# DigitalCarrierPlug.net
KiCad netlist of a schematic drawn in Altium Designer
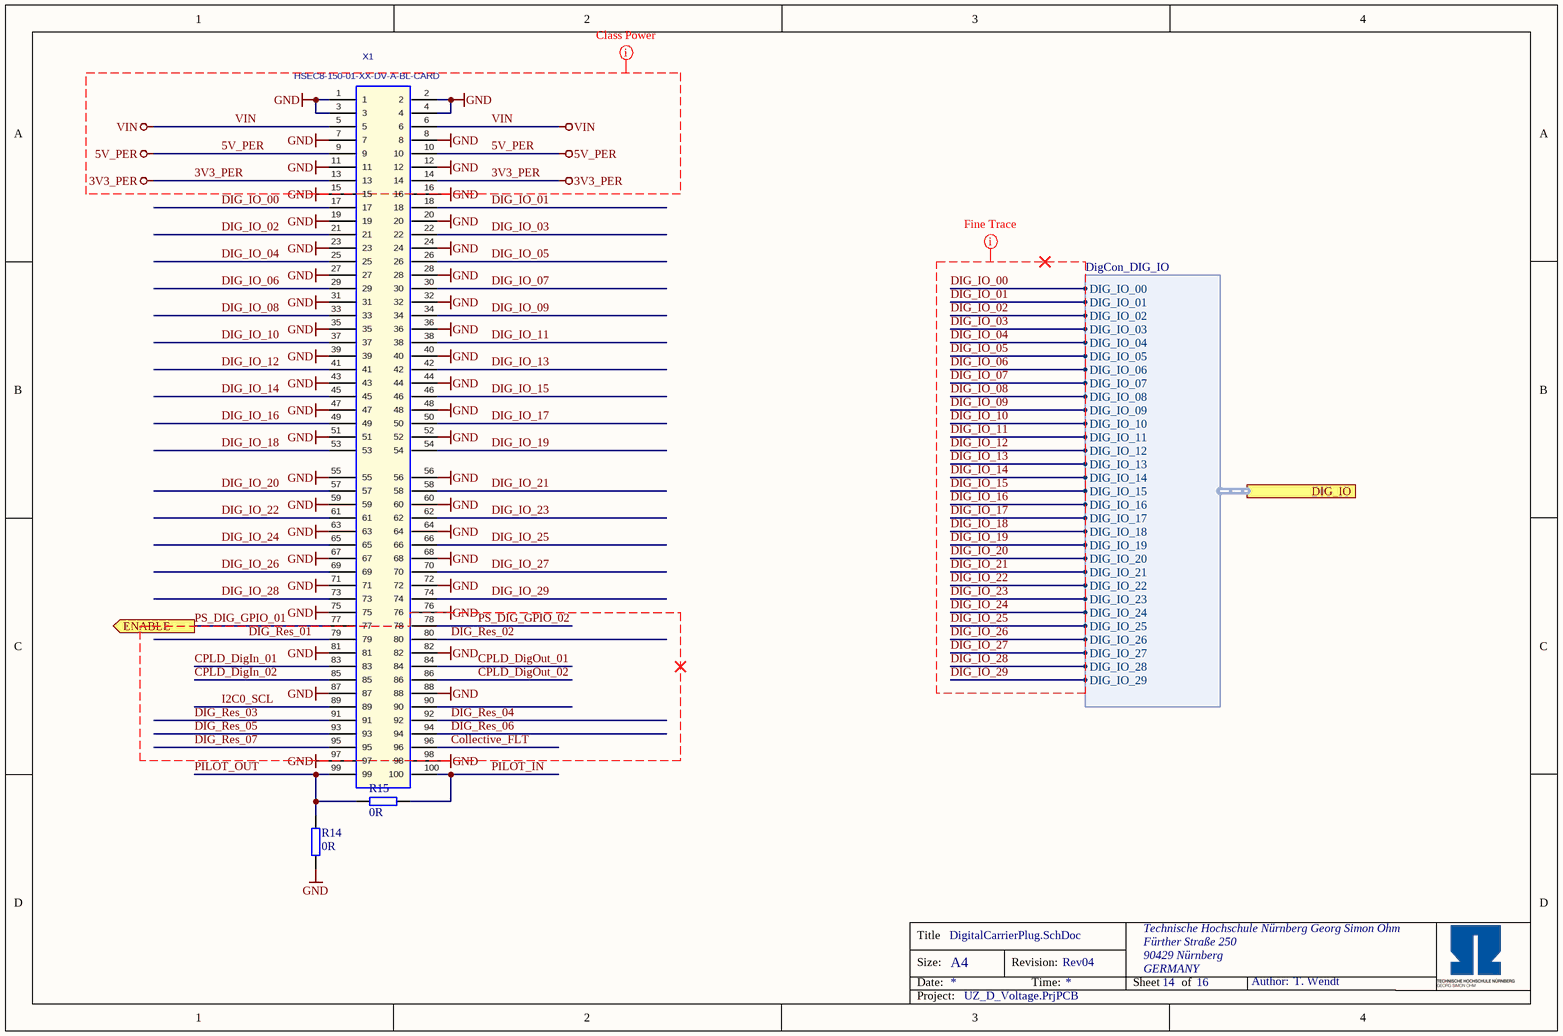
[diagram p0: DigitalCarrierPlug.SchDoc]

(export (version "E")
  (design (tool "Eeschema 10.0.6"))
  (components
    (comp (ref "R14")
      (value "0R")
      (footprint "RES 0603_1608")
      (description "SMD resistor E24 series")
      (fields
        (field (name "MANUFACTURER PART NUMBER") "RC0603JR-070RL")
        (field (name "MANUFACTURER") "YAGEO")
        (field (name "CREATED FROM") "MGremer")
      )
      (libsource (lib "user") (part "Resistor"))
    )
    (comp (ref "R15")
      (value "0R")
      (footprint "RES 0603_1608")
      (description "SMD resistor E24 series")
      (fields
        (field (name "MANUFACTURER PART NUMBER") "RC0603JR-070RL")
        (field (name "MANUFACTURER") "YAGEO")
        (field (name "CREATED FROM") "MGremer")
      )
      (libsource (lib "user") (part "Resistor"))
    )
    (comp (ref "X1")
      (value "HSEC8-150-01-XX-DV-A-BL-CARD")
      (footprint "HSEC8-150-01-XX-DV-A-BL-CARD")
      (description "Mating Card Layout for HSEC8-150-01-XX-DV-A-BL")
      (fields
        (field (name "MANUFACTURER") "SAMTEC")
        (field (name "CREATED") "2018_04_23_AGeiger")
        (field (name "CREATED FROM") "T. Wendt")
      )
      (libsource (lib "user") (part "HSEC8-150-01-XX-DV-A-BL-CARD"))
    )
  )
  (nets
    (net (code "2") (name "/CPLD_DigIn_01") (class "Default")
      (node (ref "X1") (pin "83") (pinfunction "83_83") (pintype "passive"))
    )
    (net (code "3") (name "/CPLD_DigIn_02") (class "Default")
      (node (ref "X1") (pin "85") (pinfunction "85_85") (pintype "passive"))
    )
    (net (code "4") (name "/CPLD_DigOut_01") (class "Default")
      (node (ref "X1") (pin "84") (pinfunction "84_84") (pintype "passive"))
    )
    (net (code "5") (name "/CPLD_DigOut_02") (class "Default")
      (node (ref "X1") (pin "86") (pinfunction "86_86") (pintype "passive"))
    )
    (net (code "6") (name "/Collective_FLT") (class "Default")
      (node (ref "X1") (pin "96") (pinfunction "96_96") (pintype "passive"))
    )
    (net (code "7") (name "/DIG_IO_00") (class "Default")
      (node (ref "X1") (pin "17") (pinfunction "17_17") (pintype "passive"))
    )
    (net (code "8") (name "/DIG_IO_01") (class "Default")
      (node (ref "X1") (pin "18") (pinfunction "18_18") (pintype "passive"))
    )
    (net (code "9") (name "/DIG_IO_02") (class "Default")
      (node (ref "X1") (pin "21") (pinfunction "21_21") (pintype "passive"))
    )
    (net (code "10") (name "/DIG_IO_03") (class "Default")
      (node (ref "X1") (pin "22") (pinfunction "22_22") (pintype "passive"))
    )
    (net (code "11") (name "/DIG_IO_04") (class "Default")
      (node (ref "X1") (pin "25") (pinfunction "25_25") (pintype "passive"))
    )
    (net (code "12") (name "/DIG_IO_05") (class "Default")
      (node (ref "X1") (pin "26") (pinfunction "26_26") (pintype "passive"))
    )
    (net (code "13") (name "/DIG_IO_06") (class "Default")
      (node (ref "X1") (pin "29") (pinfunction "29_29") (pintype "passive"))
    )
    (net (code "14") (name "/DIG_IO_07") (class "Default")
      (node (ref "X1") (pin "30") (pinfunction "30_30") (pintype "passive"))
    )
    (net (code "15") (name "/DIG_IO_08") (class "Default")
      (node (ref "X1") (pin "33") (pinfunction "33_33") (pintype "passive"))
    )
    (net (code "16") (name "/DIG_IO_09") (class "Default")
      (node (ref "X1") (pin "34") (pinfunction "34_34") (pintype "passive"))
    )
    (net (code "17") (name "/DIG_IO_10") (class "Default")
      (node (ref "X1") (pin "37") (pinfunction "37_37") (pintype "passive"))
    )
    (net (code "18") (name "/DIG_IO_11") (class "Default")
      (node (ref "X1") (pin "38") (pinfunction "38_38") (pintype "passive"))
    )
    (net (code "19") (name "/DIG_IO_12") (class "Default")
      (node (ref "X1") (pin "41") (pinfunction "41_41") (pintype "passive"))
    )
    (net (code "20") (name "/DIG_IO_13") (class "Default")
      (node (ref "X1") (pin "42") (pinfunction "42_42") (pintype "passive"))
    )
    (net (code "21") (name "/DIG_IO_14") (class "Default")
      (node (ref "X1") (pin "45") (pinfunction "45_45") (pintype "passive"))
    )
    (net (code "22") (name "/DIG_IO_15") (class "Default")
      (node (ref "X1") (pin "46") (pinfunction "46_46") (pintype "passive"))
    )
    (net (code "23") (name "/DIG_IO_16") (class "Default")
      (node (ref "X1") (pin "49") (pinfunction "49_49") (pintype "passive"))
    )
    (net (code "24") (name "/DIG_IO_17") (class "Default")
      (node (ref "X1") (pin "50") (pinfunction "50_50") (pintype "passive"))
    )
    (net (code "25") (name "/DIG_IO_18") (class "Default")
      (node (ref "X1") (pin "53") (pinfunction "53_53") (pintype "passive"))
    )
    (net (code "26") (name "/DIG_IO_19") (class "Default")
      (node (ref "X1") (pin "54") (pinfunction "54_54") (pintype "passive"))
    )
    (net (code "27") (name "/DIG_IO_20") (class "Default")
      (node (ref "X1") (pin "57") (pinfunction "57_57") (pintype "passive"))
    )
    (net (code "28") (name "/DIG_IO_21") (class "Default")
      (node (ref "X1") (pin "58") (pinfunction "58_58") (pintype "passive"))
    )
    (net (code "29") (name "/DIG_IO_22") (class "Default")
      (node (ref "X1") (pin "61") (pinfunction "61_61") (pintype "passive"))
    )
    (net (code "30") (name "/DIG_IO_23") (class "Default")
      (node (ref "X1") (pin "62") (pinfunction "62_62") (pintype "passive"))
    )
    (net (code "31") (name "/DIG_IO_24") (class "Default")
      (node (ref "X1") (pin "65") (pinfunction "65_65") (pintype "passive"))
    )
    (net (code "32") (name "/DIG_IO_25") (class "Default")
      (node (ref "X1") (pin "66") (pinfunction "66_66") (pintype "passive"))
    )
    (net (code "33") (name "/DIG_IO_26") (class "Default")
      (node (ref "X1") (pin "69") (pinfunction "69_69") (pintype "passive"))
    )
    (net (code "34") (name "/DIG_IO_27") (class "Default")
      (node (ref "X1") (pin "70") (pinfunction "70_70") (pintype "passive"))
    )
    (net (code "35") (name "/DIG_IO_28") (class "Default")
      (node (ref "X1") (pin "73") (pinfunction "73_73") (pintype "passive"))
    )
    (net (code "36") (name "/DIG_IO_29") (class "Default")
      (node (ref "X1") (pin "74") (pinfunction "74_74") (pintype "passive"))
    )
    (net (code "37") (name "/DIG_Res_01") (class "Default")
      (node (ref "X1") (pin "79") (pinfunction "79_79") (pintype "passive"))
    )
    (net (code "38") (name "/DIG_Res_02") (class "Default")
      (node (ref "X1") (pin "80") (pinfunction "80_80") (pintype "passive"))
    )
    (net (code "39") (name "/DIG_Res_03") (class "Default")
      (node (ref "X1") (pin "91") (pinfunction "91_91") (pintype "passive"))
    )
    (net (code "40") (name "/DIG_Res_04") (class "Default")
      (node (ref "X1") (pin "92") (pinfunction "92_92") (pintype "passive"))
    )
    (net (code "41") (name "/DIG_Res_05") (class "Default")
      (node (ref "X1") (pin "93") (pinfunction "93_93") (pintype "passive"))
    )
    (net (code "42") (name "/DIG_Res_06") (class "Default")
      (node (ref "X1") (pin "94") (pinfunction "94_94") (pintype "passive"))
    )
    (net (code "43") (name "/DIG_Res_07") (class "Default")
      (node (ref "X1") (pin "95") (pinfunction "95_95") (pintype "passive"))
    )
    (net (code "44") (name "/I2C0_SCL") (class "Default")
      (node (ref "X1") (pin "89") (pinfunction "89_89") (pintype "passive"))
    )
    (net (code "45") (name "/PILOT_IN") (class "Default")
      (node (ref "R15") (pin "1") (pinfunction "1_1") (pintype "passive"))
      (node (ref "X1") (pin "100") (pinfunction "100_100") (pintype "passive"))
    )
    (net (code "46") (name "/PILOT_OUT") (class "Default")
      (node (ref "R14") (pin "2") (pinfunction "2_2") (pintype "passive"))
      (node (ref "R15") (pin "2") (pinfunction "2_2") (pintype "passive"))
      (node (ref "X1") (pin "99") (pinfunction "99_99") (pintype "passive"))
    )
    (net (code "47") (name "/PS_DIG_GPIO_01") (class "Default")
      (node (ref "X1") (pin "77") (pinfunction "77_77") (pintype "passive"))
    )
    (net (code "48") (name "/PS_DIG_GPIO_02") (class "Default")
      (node (ref "X1") (pin "78") (pinfunction "78_78") (pintype "passive"))
    )
    (net (code "50") (name "3V3_PER") (class "Default")
      (node (ref "X1") (pin "13") (pinfunction "13_13") (pintype "passive"))
      (node (ref "X1") (pin "14") (pinfunction "14_14") (pintype "passive"))
    )
    (net (code "51") (name "5V_PER") (class "Default")
      (node (ref "X1") (pin "10") (pinfunction "10_10") (pintype "passive"))
      (node (ref "X1") (pin "9") (pinfunction "9_9") (pintype "passive"))
    )
    (net (code "52") (name "GND") (class "Default")
      (node (ref "R14") (pin "1") (pinfunction "1_1") (pintype "passive"))
      (node (ref "X1") (pin "1") (pinfunction "1_1") (pintype "passive"))
      (node (ref "X1") (pin "11") (pinfunction "11_11") (pintype "passive"))
      (node (ref "X1") (pin "12") (pinfunction "12_12") (pintype "passive"))
      (node (ref "X1") (pin "15") (pinfunction "15_15") (pintype "passive"))
      (node (ref "X1") (pin "16") (pinfunction "16_16") (pintype "passive"))
      (node (ref "X1") (pin "19") (pinfunction "19_19") (pintype "passive"))
      (node (ref "X1") (pin "2") (pinfunction "2_2") (pintype "passive"))
      (node (ref "X1") (pin "20") (pinfunction "20_20") (pintype "passive"))
      (node (ref "X1") (pin "23") (pinfunction "23_23") (pintype "passive"))
      (node (ref "X1") (pin "24") (pinfunction "24_24") (pintype "passive"))
      (node (ref "X1") (pin "27") (pinfunction "27_27") (pintype "passive"))
      (node (ref "X1") (pin "28") (pinfunction "28_28") (pintype "passive"))
      (node (ref "X1") (pin "3") (pinfunction "3_3") (pintype "passive"))
      (node (ref "X1") (pin "31") (pinfunction "31_31") (pintype "passive"))
      (node (ref "X1") (pin "32") (pinfunction "32_32") (pintype "passive"))
      (node (ref "X1") (pin "35") (pinfunction "35_35") (pintype "passive"))
      (node (ref "X1") (pin "36") (pinfunction "36_36") (pintype "passive"))
      (node (ref "X1") (pin "39") (pinfunction "39_39") (pintype "passive"))
      (node (ref "X1") (pin "4") (pinfunction "4_4") (pintype "passive"))
      (node (ref "X1") (pin "40") (pinfunction "40_40") (pintype "passive"))
      (node (ref "X1") (pin "43") (pinfunction "43_43") (pintype "passive"))
      (node (ref "X1") (pin "44") (pinfunction "44_44") (pintype "passive"))
      (node (ref "X1") (pin "47") (pinfunction "47_47") (pintype "passive"))
      (node (ref "X1") (pin "48") (pinfunction "48_48") (pintype "passive"))
      (node (ref "X1") (pin "51") (pinfunction "51_51") (pintype "passive"))
      (node (ref "X1") (pin "52") (pinfunction "52_52") (pintype "passive"))
      (node (ref "X1") (pin "55") (pinfunction "55_55") (pintype "passive"))
      (node (ref "X1") (pin "56") (pinfunction "56_56") (pintype "passive"))
      (node (ref "X1") (pin "59") (pinfunction "59_59") (pintype "passive"))
      (node (ref "X1") (pin "60") (pinfunction "60_60") (pintype "passive"))
      (node (ref "X1") (pin "63") (pinfunction "63_63") (pintype "passive"))
      (node (ref "X1") (pin "64") (pinfunction "64_64") (pintype "passive"))
      (node (ref "X1") (pin "67") (pinfunction "67_67") (pintype "passive"))
      (node (ref "X1") (pin "68") (pinfunction "68_68") (pintype "passive"))
      (node (ref "X1") (pin "7") (pinfunction "7_7") (pintype "passive"))
      (node (ref "X1") (pin "71") (pinfunction "71_71") (pintype "passive"))
      (node (ref "X1") (pin "72") (pinfunction "72_72") (pintype "passive"))
      (node (ref "X1") (pin "75") (pinfunction "75_75") (pintype "passive"))
      (node (ref "X1") (pin "76") (pinfunction "76_76") (pintype "passive"))
      (node (ref "X1") (pin "8") (pinfunction "8_8") (pintype "passive"))
      (node (ref "X1") (pin "81") (pinfunction "81_81") (pintype "passive"))
      (node (ref "X1") (pin "82") (pinfunction "82_82") (pintype "passive"))
      (node (ref "X1") (pin "87") (pinfunction "87_87") (pintype "passive"))
      (node (ref "X1") (pin "88") (pinfunction "88_88") (pintype "passive"))
      (node (ref "X1") (pin "97") (pinfunction "97_97") (pintype "passive"))
      (node (ref "X1") (pin "98") (pinfunction "98_98") (pintype "passive"))
    )
    (net (code "53") (name "VIN") (class "Default")
      (node (ref "X1") (pin "5") (pinfunction "5_5") (pintype "passive"))
      (node (ref "X1") (pin "6") (pinfunction "6_6") (pintype "passive"))
    )
    (net (code "54") (name "unconnected-(X1-Pad90)") (class "Default")
      (node (ref "X1") (pin "90") (pinfunction "90_90") (pintype "passive"))
    )
  )
)
